# SCH_ProbeConverter_2023-01-18_1.net
KiCad netlist of a schematic drawn in EasyEDA
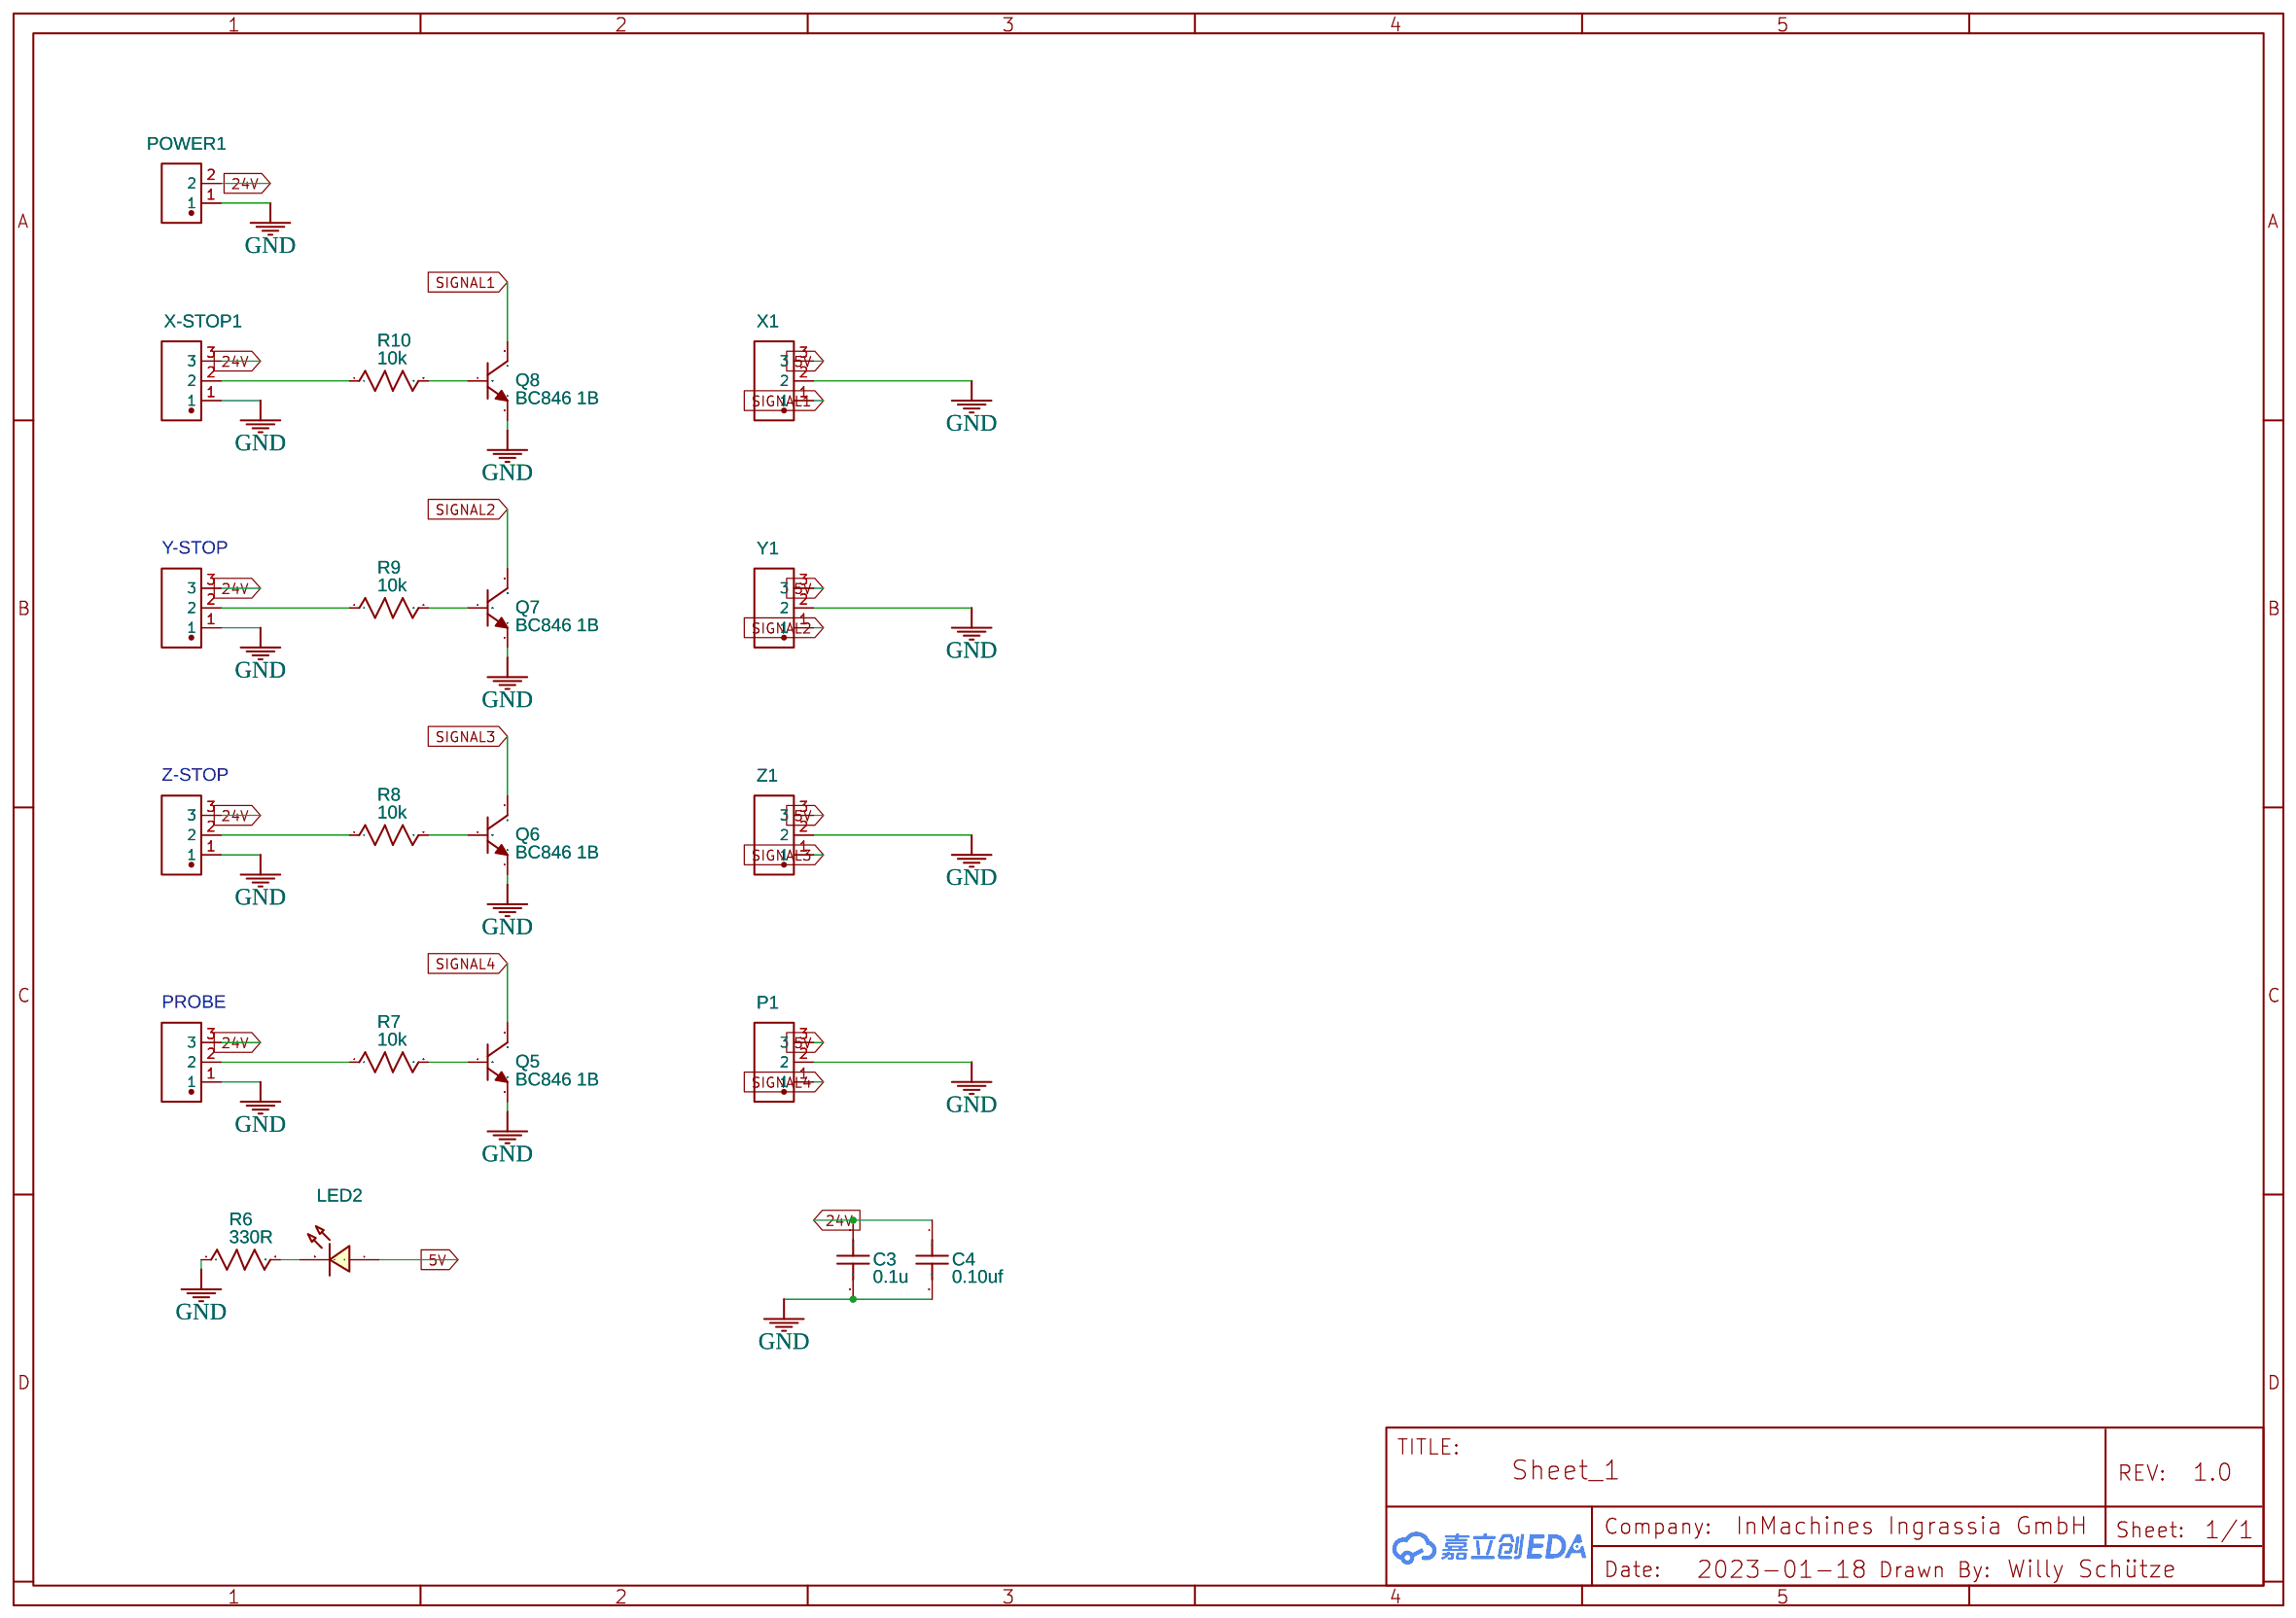
[diagram p0: schematic sheet]

(export (version "E")
  (design (tool "Eeschema 10.0.6"))
  (components
    (comp (ref "C3") (value "0.1u") (libsource (lib "") (part "C_1206_US")))
    (comp (ref "C4") (value "0.10uf") (libsource (lib "") (part "C_1206_US")))
    (comp (ref "LED2")
      (value "SZYY1206G")
      (fields (field (name "BOM_Supplier Part") "C434439"))
      (libsource (lib "") (part "SZYY1206G"))
    )
    (comp (ref "P1")
      (value "KF2EDGR-5.08-3P")
      (fields (field (name "BOM_Supplier Part") "C441205"))
      (libsource (lib "") (part "KF2EDGR-5.08-3P_2"))
    )
    (comp (ref "POWER1")
      (value "KF2EDGR-5.08-2P")
      (fields (field (name "BOM_Supplier Part") "C441204"))
      (libsource (lib "") (part "KF2EDGR-5.08-2P"))
    )
    (comp (ref "PROBE1")
      (value "KF2EDGR-5.08-3P")
      (fields (field (name "BOM_Supplier Part") "C441205"))
      (libsource (lib "") (part "KF2EDGR-5.08-3P_4"))
    )
    (comp (ref "Q5")
      (value "BC846 1B")
      (fields (field (name "BOM_Supplier Part") "C8573"))
      (libsource (lib "") (part "BC846 1B"))
    )
    (comp (ref "Q6")
      (value "BC846 1B")
      (fields (field (name "BOM_Supplier Part") "C8573"))
      (libsource (lib "") (part "BC846 1B"))
    )
    (comp (ref "Q7")
      (value "BC846 1B")
      (fields (field (name "BOM_Supplier Part") "C8573"))
      (libsource (lib "") (part "BC846 1B"))
    )
    (comp (ref "Q8")
      (value "BC846 1B")
      (fields (field (name "BOM_Supplier Part") "C8573"))
      (libsource (lib "") (part "BC846 1B"))
    )
    (comp (ref "R6") (value "330R") (libsource (lib "") (part "R_1206_US")))
    (comp (ref "R7") (value "10k") (libsource (lib "") (part "R_1206_US")))
    (comp (ref "R8") (value "10k") (libsource (lib "") (part "R_1206_US")))
    (comp (ref "R9") (value "10k") (libsource (lib "") (part "R_1206_US")))
    (comp (ref "R10") (value "10k") (libsource (lib "") (part "R_1206_US")))
    (comp (ref "X-STOP1")
      (value "KF2EDGR-5.08-3P")
      (fields (field (name "BOM_Supplier Part") "C441205"))
      (libsource (lib "") (part "KF2EDGR-5.08-3P_3"))
    )
    (comp (ref "X1")
      (value "KF2EDGR-5.08-3P")
      (fields (field (name "BOM_Supplier Part") "C441205"))
      (libsource (lib "") (part "KF2EDGR-5.08-3P_5"))
    )
    (comp (ref "Y-STOP1")
      (value "KF2EDGR-5.08-3P")
      (fields (field (name "BOM_Supplier Part") "C441205"))
      (libsource (lib "") (part "KF2EDGR-5.08-3P"))
    )
    (comp (ref "Y1")
      (value "KF2EDGR-5.08-3P")
      (fields (field (name "BOM_Supplier Part") "C441205"))
      (libsource (lib "") (part "KF2EDGR-5.08-3P_7"))
    )
    (comp (ref "Z-STOP1")
      (value "KF2EDGR-5.08-3P")
      (fields (field (name "BOM_Supplier Part") "C441205"))
      (libsource (lib "") (part "KF2EDGR-5.08-3P_1"))
    )
    (comp (ref "Z1")
      (value "KF2EDGR-5.08-3P")
      (fields (field (name "BOM_Supplier Part") "C441205"))
      (libsource (lib "") (part "KF2EDGR-5.08-3P_6"))
    )
  )
  (nets
    (net (code "1") (name "5V") (class "Default")
      (node (ref "LED2") (pin "1") (pinfunction "+_1") (pintype "unspecified"))
      (node (ref "P1") (pin "3") (pinfunction "3_3") (pintype "unspecified"))
      (node (ref "X1") (pin "3") (pinfunction "3_3") (pintype "unspecified"))
      (node (ref "Y1") (pin "3") (pinfunction "3_3") (pintype "unspecified"))
      (node (ref "Z1") (pin "3") (pinfunction "3_3") (pintype "unspecified"))
    )
    (net (code "2") (name "24V") (class "Default")
      (node (ref "C3") (pin "1") (pinfunction "1_1") (pintype "unspecified"))
      (node (ref "C4") (pin "1") (pinfunction "1_1") (pintype "unspecified"))
      (node (ref "POWER1") (pin "2") (pinfunction "2_2") (pintype "unspecified"))
      (node (ref "PROBE1") (pin "3") (pinfunction "3_3") (pintype "unspecified"))
      (node (ref "X-STOP1") (pin "3") (pinfunction "3_3") (pintype "unspecified"))
      (node (ref "Y-STOP1") (pin "3") (pinfunction "3_3") (pintype "unspecified"))
      (node (ref "Z-STOP1") (pin "3") (pinfunction "3_3") (pintype "unspecified"))
    )
    (net (code "3") (name "GND") (class "Default")
      (node (ref "C3") (pin "2") (pinfunction "2_2") (pintype "unspecified"))
      (node (ref "C4") (pin "2") (pinfunction "2_2") (pintype "unspecified"))
      (node (ref "P1") (pin "2") (pinfunction "2_2") (pintype "unspecified"))
      (node (ref "POWER1") (pin "1") (pinfunction "1_1") (pintype "unspecified"))
      (node (ref "PROBE1") (pin "1") (pinfunction "1_1") (pintype "unspecified"))
      (node (ref "Q5") (pin "2") (pinfunction "E_2") (pintype "unspecified"))
      (node (ref "Q6") (pin "2") (pinfunction "E_2") (pintype "unspecified"))
      (node (ref "Q7") (pin "2") (pinfunction "E_2") (pintype "unspecified"))
      (node (ref "Q8") (pin "2") (pinfunction "E_2") (pintype "unspecified"))
      (node (ref "R6") (pin "1") (pinfunction "1_1") (pintype "unspecified"))
      (node (ref "X-STOP1") (pin "1") (pinfunction "1_1") (pintype "unspecified"))
      (node (ref "X1") (pin "2") (pinfunction "2_2") (pintype "unspecified"))
      (node (ref "Y-STOP1") (pin "1") (pinfunction "1_1") (pintype "unspecified"))
      (node (ref "Y1") (pin "2") (pinfunction "2_2") (pintype "unspecified"))
      (node (ref "Z-STOP1") (pin "1") (pinfunction "1_1") (pintype "unspecified"))
      (node (ref "Z1") (pin "2") (pinfunction "2_2") (pintype "unspecified"))
    )
    (net (code "4") (name "Net-(LED2--)") (class "Default")
      (node (ref "LED2") (pin "2") (pinfunction "-_2") (pintype "unspecified"))
      (node (ref "R6") (pin "2") (pinfunction "2_2") (pintype "unspecified"))
    )
    (net (code "5") (name "Net-(PROBE1-Pad2)") (class "Default")
      (node (ref "PROBE1") (pin "2") (pinfunction "2_2") (pintype "unspecified"))
      (node (ref "R7") (pin "1") (pinfunction "1_1") (pintype "unspecified"))
    )
    (net (code "6") (name "Net-(Q5-B)") (class "Default")
      (node (ref "Q5") (pin "1") (pinfunction "B_1") (pintype "unspecified"))
      (node (ref "R7") (pin "2") (pinfunction "2_2") (pintype "unspecified"))
    )
    (net (code "7") (name "Net-(Q6-B)") (class "Default")
      (node (ref "Q6") (pin "1") (pinfunction "B_1") (pintype "unspecified"))
      (node (ref "R8") (pin "2") (pinfunction "2_2") (pintype "unspecified"))
    )
    (net (code "8") (name "Net-(Q7-B)") (class "Default")
      (node (ref "Q7") (pin "1") (pinfunction "B_1") (pintype "unspecified"))
      (node (ref "R9") (pin "2") (pinfunction "2_2") (pintype "unspecified"))
    )
    (net (code "9") (name "Net-(Q8-B)") (class "Default")
      (node (ref "Q8") (pin "1") (pinfunction "B_1") (pintype "unspecified"))
      (node (ref "R10") (pin "2") (pinfunction "2_2") (pintype "unspecified"))
    )
    (net (code "10") (name "Net-(R8-Pad1)") (class "Default")
      (node (ref "R8") (pin "1") (pinfunction "1_1") (pintype "unspecified"))
      (node (ref "Z-STOP1") (pin "2") (pinfunction "2_2") (pintype "unspecified"))
    )
    (net (code "11") (name "Net-(R9-Pad1)") (class "Default")
      (node (ref "R9") (pin "1") (pinfunction "1_1") (pintype "unspecified"))
      (node (ref "Y-STOP1") (pin "2") (pinfunction "2_2") (pintype "unspecified"))
    )
    (net (code "12") (name "Net-(R10-Pad1)") (class "Default")
      (node (ref "R10") (pin "1") (pinfunction "1_1") (pintype "unspecified"))
      (node (ref "X-STOP1") (pin "2") (pinfunction "2_2") (pintype "unspecified"))
    )
    (net (code "13") (name "SIGNAL1") (class "Default")
      (node (ref "Q8") (pin "3") (pinfunction "C_3") (pintype "unspecified"))
      (node (ref "X1") (pin "1") (pinfunction "1_1") (pintype "unspecified"))
    )
    (net (code "14") (name "SIGNAL2") (class "Default")
      (node (ref "Q7") (pin "3") (pinfunction "C_3") (pintype "unspecified"))
      (node (ref "Y1") (pin "1") (pinfunction "1_1") (pintype "unspecified"))
    )
    (net (code "15") (name "SIGNAL3") (class "Default")
      (node (ref "Q6") (pin "3") (pinfunction "C_3") (pintype "unspecified"))
      (node (ref "Z1") (pin "1") (pinfunction "1_1") (pintype "unspecified"))
    )
    (net (code "16") (name "SIGNAL4") (class "Default")
      (node (ref "P1") (pin "1") (pinfunction "1_1") (pintype "unspecified"))
      (node (ref "Q5") (pin "3") (pinfunction "C_3") (pintype "unspecified"))
    )
  )
)
